# stand.net
KiCad netlist of a schematic drawn in Altium Designer
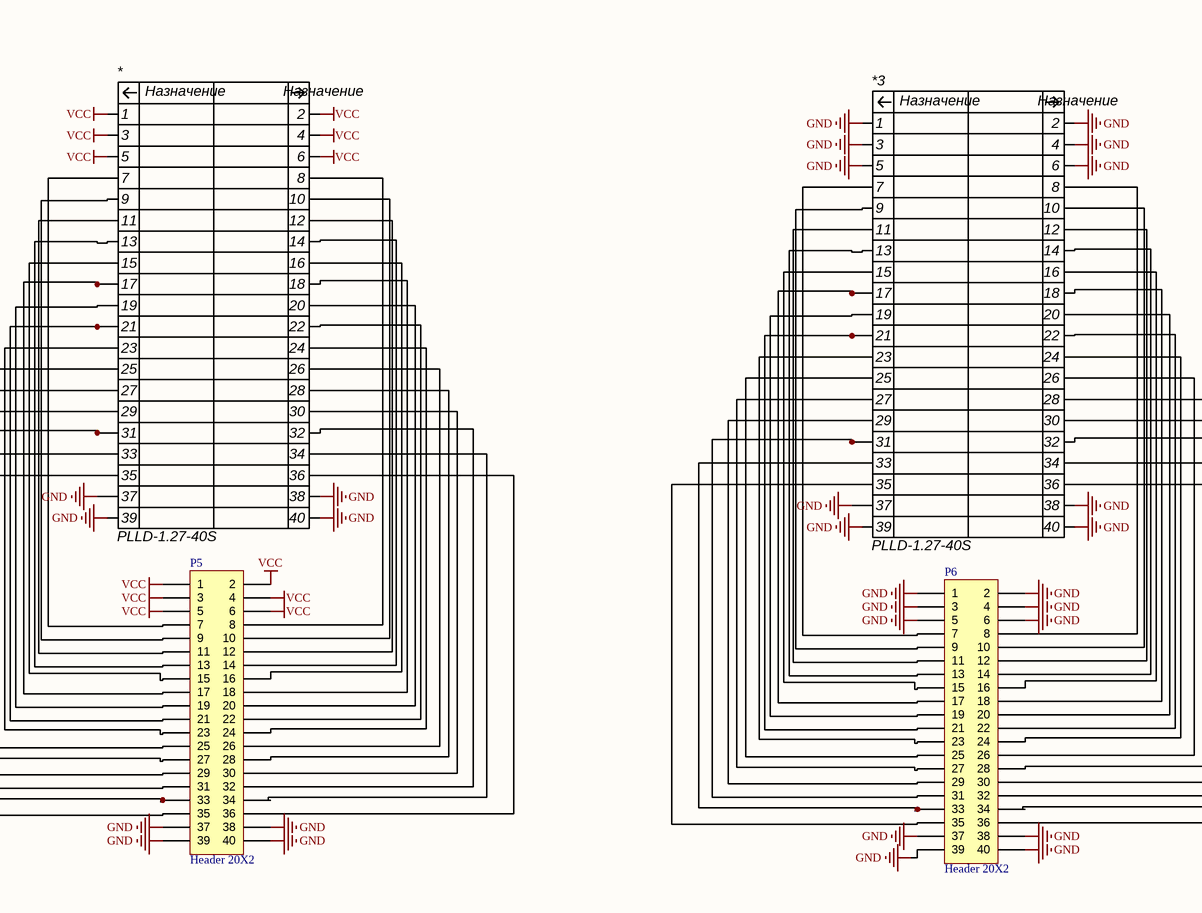
[diagram p0: stand.SchDoc, left]
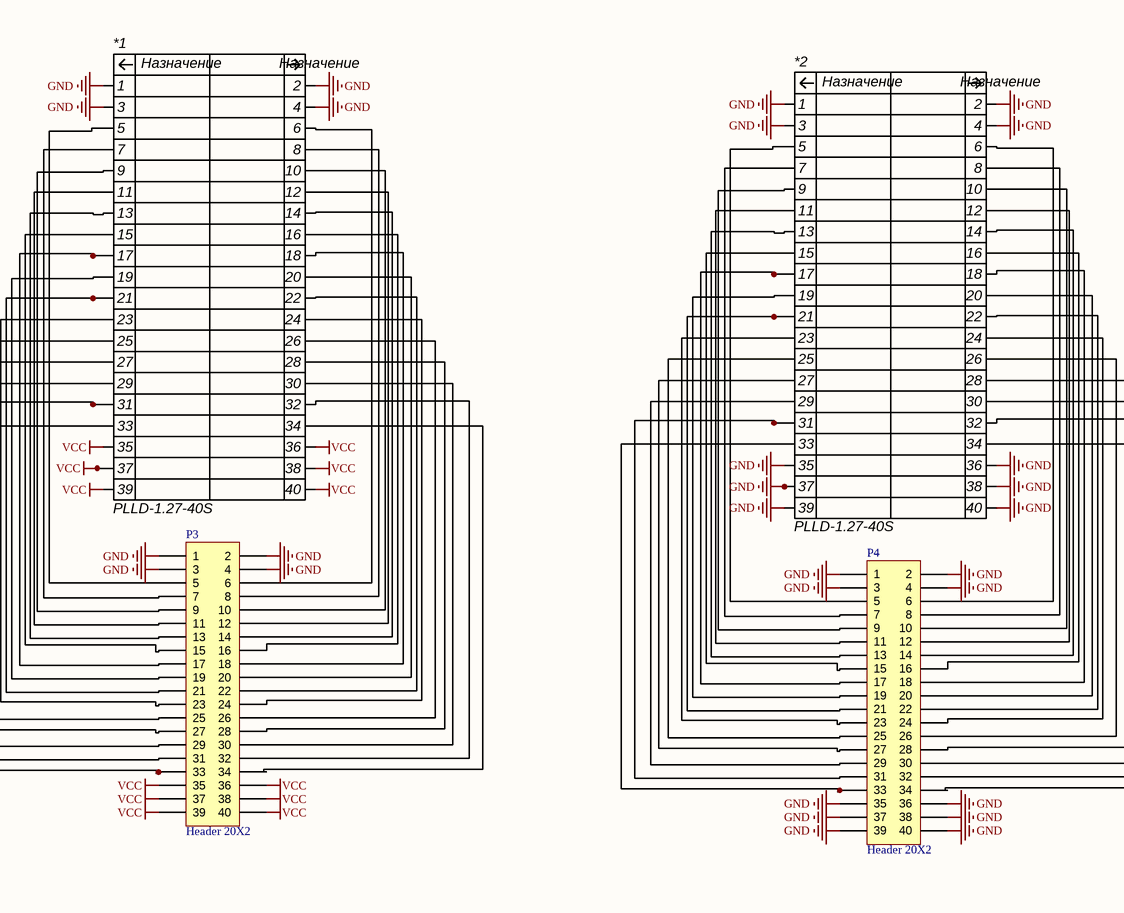
[diagram p1: stand.SchDoc, right]

(export (version "E")
  (design (tool "Eeschema 10.0.6"))
  (components
    (comp (ref "*")
      (value "PLLD-1.27-40S")
      (footprint "Headr 2x20 male")
      (libsource (lib "Разьемы_PLLD_PBD") (part "PLLD-1.27-40S"))
    )
    (comp (ref "*1")
      (value "PLLD-1.27-40S")
      (footprint "Headr 2x20 male")
      (libsource (lib "Разьемы_PLLD_PBD") (part "PLLD-1.27-40S"))
    )
    (comp (ref "*2")
      (value "PLLD-1.27-40S")
      (footprint "Headr 2x20 male")
      (libsource (lib "Разьемы_PLLD_PBD") (part "PLLD-1.27-40S"))
    )
    (comp (ref "*3")
      (value "PLLD-1.27-40S")
      (footprint "Headr 2x20 male")
      (libsource (lib "Разьемы_PLLD_PBD") (part "PLLD-1.27-40S"))
    )
    (comp (ref "P3")
      (value "Header 20X2")
      (footprint "HDR2X20")
      (description "Header, 20-Pin, Dual row")
      (fields (field (name "PUBLISHER") "Altium Limited"))
      (libsource (lib "Miscellaneous Connectors") (part "Header 20X2"))
    )
    (comp (ref "P4")
      (value "Header 20X2")
      (footprint "HDR2X20")
      (description "Header, 20-Pin, Dual row")
      (fields (field (name "PUBLISHER") "Altium Limited"))
      (libsource (lib "Miscellaneous Connectors") (part "Header 20X2"))
    )
    (comp (ref "P5")
      (value "Header 20X2")
      (footprint "HDR2X20")
      (description "Header, 20-Pin, Dual row")
      (fields (field (name "PUBLISHER") "Altium Limited"))
      (libsource (lib "Miscellaneous Connectors") (part "Header 20X2"))
    )
    (comp (ref "P6")
      (value "Header 20X2")
      (footprint "HDR2X20")
      (description "Header, 20-Pin, Dual row")
      (fields (field (name "PUBLISHER") "Altium Limited"))
      (libsource (lib "Miscellaneous Connectors") (part "Header 20X2"))
    )
  )
  (nets
    (net (code "1") (name "GND") (class "Default")
      (node (ref "*") (pin "37") (pinfunction "37_37") (pintype "passive"))
      (node (ref "*") (pin "38") (pinfunction "38_38") (pintype "passive"))
      (node (ref "*") (pin "39") (pinfunction "39_39") (pintype "passive"))
      (node (ref "*") (pin "40") (pinfunction "40_40") (pintype "passive"))
      (node (ref "*1") (pin "1") (pinfunction "1_1") (pintype "passive"))
      (node (ref "*1") (pin "2") (pinfunction "2_2") (pintype "passive"))
      (node (ref "*1") (pin "3") (pinfunction "3_3") (pintype "passive"))
      (node (ref "*1") (pin "4") (pinfunction "4_4") (pintype "passive"))
      (node (ref "*2") (pin "1") (pinfunction "1_1") (pintype "passive"))
      (node (ref "*2") (pin "2") (pinfunction "2_2") (pintype "passive"))
      (node (ref "*2") (pin "3") (pinfunction "3_3") (pintype "passive"))
      (node (ref "*2") (pin "35") (pinfunction "35_35") (pintype "passive"))
      (node (ref "*2") (pin "36") (pinfunction "36_36") (pintype "passive"))
      (node (ref "*2") (pin "37") (pinfunction "37_37") (pintype "passive"))
      (node (ref "*2") (pin "38") (pinfunction "38_38") (pintype "passive"))
      (node (ref "*2") (pin "39") (pinfunction "39_39") (pintype "passive"))
      (node (ref "*2") (pin "4") (pinfunction "4_4") (pintype "passive"))
      (node (ref "*2") (pin "40") (pinfunction "40_40") (pintype "passive"))
      (node (ref "*3") (pin "1") (pinfunction "1_1") (pintype "passive"))
      (node (ref "*3") (pin "2") (pinfunction "2_2") (pintype "passive"))
      (node (ref "*3") (pin "3") (pinfunction "3_3") (pintype "passive"))
      (node (ref "*3") (pin "37") (pinfunction "37_37") (pintype "passive"))
      (node (ref "*3") (pin "38") (pinfunction "38_38") (pintype "passive"))
      (node (ref "*3") (pin "39") (pinfunction "39_39") (pintype "passive"))
      (node (ref "*3") (pin "4") (pinfunction "4_4") (pintype "passive"))
      (node (ref "*3") (pin "40") (pinfunction "40_40") (pintype "passive"))
      (node (ref "*3") (pin "5") (pinfunction "5_5") (pintype "passive"))
      (node (ref "*3") (pin "6") (pinfunction "6_6") (pintype "passive"))
      (node (ref "P3") (pin "1") (pinfunction "1_1") (pintype "passive"))
      (node (ref "P3") (pin "2") (pinfunction "2_2") (pintype "passive"))
      (node (ref "P3") (pin "3") (pinfunction "3_3") (pintype "passive"))
      (node (ref "P3") (pin "4") (pinfunction "4_4") (pintype "passive"))
      (node (ref "P4") (pin "1") (pinfunction "1_1") (pintype "passive"))
      (node (ref "P4") (pin "2") (pinfunction "2_2") (pintype "passive"))
      (node (ref "P4") (pin "3") (pinfunction "3_3") (pintype "passive"))
      (node (ref "P4") (pin "35") (pinfunction "35_35") (pintype "passive"))
      (node (ref "P4") (pin "36") (pinfunction "36_36") (pintype "passive"))
      (node (ref "P4") (pin "37") (pinfunction "37_37") (pintype "passive"))
      (node (ref "P4") (pin "38") (pinfunction "38_38") (pintype "passive"))
      (node (ref "P4") (pin "39") (pinfunction "39_39") (pintype "passive"))
      (node (ref "P4") (pin "4") (pinfunction "4_4") (pintype "passive"))
      (node (ref "P4") (pin "40") (pinfunction "40_40") (pintype "passive"))
      (node (ref "P5") (pin "37") (pinfunction "37_37") (pintype "passive"))
      (node (ref "P5") (pin "38") (pinfunction "38_38") (pintype "passive"))
      (node (ref "P5") (pin "39") (pinfunction "39_39") (pintype "passive"))
      (node (ref "P5") (pin "40") (pinfunction "40_40") (pintype "passive"))
      (node (ref "P6") (pin "1") (pinfunction "1_1") (pintype "passive"))
      (node (ref "P6") (pin "2") (pinfunction "2_2") (pintype "passive"))
      (node (ref "P6") (pin "3") (pinfunction "3_3") (pintype "passive"))
      (node (ref "P6") (pin "37") (pinfunction "37_37") (pintype "passive"))
      (node (ref "P6") (pin "38") (pinfunction "38_38") (pintype "passive"))
      (node (ref "P6") (pin "39") (pinfunction "39_39") (pintype "passive"))
      (node (ref "P6") (pin "4") (pinfunction "4_4") (pintype "passive"))
      (node (ref "P6") (pin "40") (pinfunction "40_40") (pintype "passive"))
      (node (ref "P6") (pin "5") (pinfunction "5_5") (pintype "passive"))
      (node (ref "P6") (pin "6") (pinfunction "6_6") (pintype "passive"))
    )
    (net (code "2") (name "Net-(*-Pad7)") (class "Default")
      (node (ref "*") (pin "7") (pinfunction "7_7") (pintype "passive"))
      (node (ref "P5") (pin "7") (pinfunction "7_7") (pintype "passive"))
    )
    (net (code "3") (name "Net-(*-Pad8)") (class "Default")
      (node (ref "*") (pin "8") (pinfunction "8_8") (pintype "passive"))
      (node (ref "P5") (pin "8") (pinfunction "8_8") (pintype "passive"))
    )
    (net (code "4") (name "Net-(*-Pad9)") (class "Default")
      (node (ref "*") (pin "9") (pinfunction "9_9") (pintype "passive"))
      (node (ref "P5") (pin "9") (pinfunction "9_9") (pintype "passive"))
    )
    (net (code "5") (name "Net-(*-Pad10)") (class "Default")
      (node (ref "*") (pin "10") (pinfunction "10_10") (pintype "passive"))
      (node (ref "P5") (pin "10") (pinfunction "10_10") (pintype "passive"))
    )
    (net (code "6") (name "Net-(*-Pad11)") (class "Default")
      (node (ref "*") (pin "11") (pinfunction "11_11") (pintype "passive"))
      (node (ref "P5") (pin "11") (pinfunction "11_11") (pintype "passive"))
    )
    (net (code "7") (name "Net-(*-Pad12)") (class "Default")
      (node (ref "*") (pin "12") (pinfunction "12_12") (pintype "passive"))
      (node (ref "P5") (pin "12") (pinfunction "12_12") (pintype "passive"))
    )
    (net (code "8") (name "Net-(*-Pad13)") (class "Default")
      (node (ref "*") (pin "13") (pinfunction "13_13") (pintype "passive"))
      (node (ref "P5") (pin "13") (pinfunction "13_13") (pintype "passive"))
    )
    (net (code "9") (name "Net-(*-Pad14)") (class "Default")
      (node (ref "*") (pin "14") (pinfunction "14_14") (pintype "passive"))
      (node (ref "P5") (pin "14") (pinfunction "14_14") (pintype "passive"))
    )
    (net (code "10") (name "Net-(*-Pad15)") (class "Default")
      (node (ref "*") (pin "15") (pinfunction "15_15") (pintype "passive"))
      (node (ref "P5") (pin "15") (pinfunction "15_15") (pintype "passive"))
    )
    (net (code "11") (name "Net-(*-Pad16)") (class "Default")
      (node (ref "*") (pin "16") (pinfunction "16_16") (pintype "passive"))
      (node (ref "P5") (pin "16") (pinfunction "16_16") (pintype "passive"))
    )
    (net (code "12") (name "Net-(*-Pad17)") (class "Default")
      (node (ref "*") (pin "17") (pinfunction "17_17") (pintype "passive"))
      (node (ref "P5") (pin "17") (pinfunction "17_17") (pintype "passive"))
    )
    (net (code "13") (name "Net-(*-Pad18)") (class "Default")
      (node (ref "*") (pin "18") (pinfunction "18_18") (pintype "passive"))
      (node (ref "P5") (pin "18") (pinfunction "18_18") (pintype "passive"))
    )
    (net (code "14") (name "Net-(*-Pad19)") (class "Default")
      (node (ref "*") (pin "19") (pinfunction "19_19") (pintype "passive"))
      (node (ref "P5") (pin "19") (pinfunction "19_19") (pintype "passive"))
    )
    (net (code "15") (name "Net-(*-Pad20)") (class "Default")
      (node (ref "*") (pin "20") (pinfunction "20_20") (pintype "passive"))
      (node (ref "P5") (pin "20") (pinfunction "20_20") (pintype "passive"))
    )
    (net (code "16") (name "Net-(*-Pad21)") (class "Default")
      (node (ref "*") (pin "21") (pinfunction "21_21") (pintype "passive"))
      (node (ref "P5") (pin "21") (pinfunction "21_21") (pintype "passive"))
    )
    (net (code "17") (name "Net-(*-Pad22)") (class "Default")
      (node (ref "*") (pin "22") (pinfunction "22_22") (pintype "passive"))
      (node (ref "P5") (pin "22") (pinfunction "22_22") (pintype "passive"))
    )
    (net (code "18") (name "Net-(*-Pad23)") (class "Default")
      (node (ref "*") (pin "23") (pinfunction "23_23") (pintype "passive"))
      (node (ref "P5") (pin "23") (pinfunction "23_23") (pintype "passive"))
    )
    (net (code "19") (name "Net-(*-Pad24)") (class "Default")
      (node (ref "*") (pin "24") (pinfunction "24_24") (pintype "passive"))
      (node (ref "P5") (pin "24") (pinfunction "24_24") (pintype "passive"))
    )
    (net (code "20") (name "Net-(*-Pad25)") (class "Default")
      (node (ref "*") (pin "25") (pinfunction "25_25") (pintype "passive"))
      (node (ref "P5") (pin "25") (pinfunction "25_25") (pintype "passive"))
    )
    (net (code "21") (name "Net-(*-Pad26)") (class "Default")
      (node (ref "*") (pin "26") (pinfunction "26_26") (pintype "passive"))
      (node (ref "P5") (pin "26") (pinfunction "26_26") (pintype "passive"))
    )
    (net (code "22") (name "Net-(*-Pad27)") (class "Default")
      (node (ref "*") (pin "27") (pinfunction "27_27") (pintype "passive"))
      (node (ref "P5") (pin "27") (pinfunction "27_27") (pintype "passive"))
    )
    (net (code "23") (name "Net-(*-Pad28)") (class "Default")
      (node (ref "*") (pin "28") (pinfunction "28_28") (pintype "passive"))
      (node (ref "P5") (pin "28") (pinfunction "28_28") (pintype "passive"))
    )
    (net (code "24") (name "Net-(*-Pad29)") (class "Default")
      (node (ref "*") (pin "29") (pinfunction "29_29") (pintype "passive"))
      (node (ref "P5") (pin "29") (pinfunction "29_29") (pintype "passive"))
    )
    (net (code "25") (name "Net-(*-Pad30)") (class "Default")
      (node (ref "*") (pin "30") (pinfunction "30_30") (pintype "passive"))
      (node (ref "P5") (pin "30") (pinfunction "30_30") (pintype "passive"))
    )
    (net (code "26") (name "Net-(*-Pad31)") (class "Default")
      (node (ref "*") (pin "31") (pinfunction "31_31") (pintype "passive"))
      (node (ref "P5") (pin "31") (pinfunction "31_31") (pintype "passive"))
    )
    (net (code "27") (name "Net-(*-Pad32)") (class "Default")
      (node (ref "*") (pin "32") (pinfunction "32_32") (pintype "passive"))
      (node (ref "P5") (pin "32") (pinfunction "32_32") (pintype "passive"))
    )
    (net (code "28") (name "Net-(*-Pad33)") (class "Default")
      (node (ref "*") (pin "33") (pinfunction "33_33") (pintype "passive"))
      (node (ref "P5") (pin "33") (pinfunction "33_33") (pintype "passive"))
    )
    (net (code "29") (name "Net-(*-Pad34)") (class "Default")
      (node (ref "*") (pin "34") (pinfunction "34_34") (pintype "passive"))
      (node (ref "P5") (pin "34") (pinfunction "34_34") (pintype "passive"))
    )
    (net (code "30") (name "Net-(*-Pad35)") (class "Default")
      (node (ref "*") (pin "35") (pinfunction "35_35") (pintype "passive"))
      (node (ref "P5") (pin "35") (pinfunction "35_35") (pintype "passive"))
    )
    (net (code "31") (name "Net-(*-Pad36)") (class "Default")
      (node (ref "*") (pin "36") (pinfunction "36_36") (pintype "passive"))
      (node (ref "P5") (pin "36") (pinfunction "36_36") (pintype "passive"))
    )
    (net (code "32") (name "Net-(*1-Pad5)") (class "Default")
      (node (ref "*1") (pin "5") (pinfunction "5_5") (pintype "passive"))
      (node (ref "P3") (pin "5") (pinfunction "5_5") (pintype "passive"))
    )
    (net (code "33") (name "Net-(*1-Pad6)") (class "Default")
      (node (ref "*1") (pin "6") (pinfunction "6_6") (pintype "passive"))
      (node (ref "P3") (pin "6") (pinfunction "6_6") (pintype "passive"))
    )
    (net (code "34") (name "Net-(*1-Pad7)") (class "Default")
      (node (ref "*1") (pin "7") (pinfunction "7_7") (pintype "passive"))
      (node (ref "P3") (pin "7") (pinfunction "7_7") (pintype "passive"))
    )
    (net (code "35") (name "Net-(*1-Pad8)") (class "Default")
      (node (ref "*1") (pin "8") (pinfunction "8_8") (pintype "passive"))
      (node (ref "P3") (pin "8") (pinfunction "8_8") (pintype "passive"))
    )
    (net (code "36") (name "Net-(*1-Pad9)") (class "Default")
      (node (ref "*1") (pin "9") (pinfunction "9_9") (pintype "passive"))
      (node (ref "P3") (pin "9") (pinfunction "9_9") (pintype "passive"))
    )
    (net (code "37") (name "Net-(*1-Pad10)") (class "Default")
      (node (ref "*1") (pin "10") (pinfunction "10_10") (pintype "passive"))
      (node (ref "P3") (pin "10") (pinfunction "10_10") (pintype "passive"))
    )
    (net (code "38") (name "Net-(*1-Pad11)") (class "Default")
      (node (ref "*1") (pin "11") (pinfunction "11_11") (pintype "passive"))
      (node (ref "P3") (pin "11") (pinfunction "11_11") (pintype "passive"))
    )
    (net (code "39") (name "Net-(*1-Pad12)") (class "Default")
      (node (ref "*1") (pin "12") (pinfunction "12_12") (pintype "passive"))
      (node (ref "P3") (pin "12") (pinfunction "12_12") (pintype "passive"))
    )
    (net (code "40") (name "Net-(*1-Pad13)") (class "Default")
      (node (ref "*1") (pin "13") (pinfunction "13_13") (pintype "passive"))
      (node (ref "P3") (pin "13") (pinfunction "13_13") (pintype "passive"))
    )
    (net (code "41") (name "Net-(*1-Pad14)") (class "Default")
      (node (ref "*1") (pin "14") (pinfunction "14_14") (pintype "passive"))
      (node (ref "P3") (pin "14") (pinfunction "14_14") (pintype "passive"))
    )
    (net (code "42") (name "Net-(*1-Pad15)") (class "Default")
      (node (ref "*1") (pin "15") (pinfunction "15_15") (pintype "passive"))
      (node (ref "P3") (pin "15") (pinfunction "15_15") (pintype "passive"))
    )
    (net (code "43") (name "Net-(*1-Pad16)") (class "Default")
      (node (ref "*1") (pin "16") (pinfunction "16_16") (pintype "passive"))
      (node (ref "P3") (pin "16") (pinfunction "16_16") (pintype "passive"))
    )
    (net (code "44") (name "Net-(*1-Pad17)") (class "Default")
      (node (ref "*1") (pin "17") (pinfunction "17_17") (pintype "passive"))
      (node (ref "P3") (pin "17") (pinfunction "17_17") (pintype "passive"))
    )
    (net (code "45") (name "Net-(*1-Pad18)") (class "Default")
      (node (ref "*1") (pin "18") (pinfunction "18_18") (pintype "passive"))
      (node (ref "P3") (pin "18") (pinfunction "18_18") (pintype "passive"))
    )
    (net (code "46") (name "Net-(*1-Pad19)") (class "Default")
      (node (ref "*1") (pin "19") (pinfunction "19_19") (pintype "passive"))
      (node (ref "P3") (pin "19") (pinfunction "19_19") (pintype "passive"))
    )
    (net (code "47") (name "Net-(*1-Pad20)") (class "Default")
      (node (ref "*1") (pin "20") (pinfunction "20_20") (pintype "passive"))
      (node (ref "P3") (pin "20") (pinfunction "20_20") (pintype "passive"))
    )
    (net (code "48") (name "Net-(*1-Pad21)") (class "Default")
      (node (ref "*1") (pin "21") (pinfunction "21_21") (pintype "passive"))
      (node (ref "P3") (pin "21") (pinfunction "21_21") (pintype "passive"))
    )
    (net (code "49") (name "Net-(*1-Pad22)") (class "Default")
      (node (ref "*1") (pin "22") (pinfunction "22_22") (pintype "passive"))
      (node (ref "P3") (pin "22") (pinfunction "22_22") (pintype "passive"))
    )
    (net (code "50") (name "Net-(*1-Pad23)") (class "Default")
      (node (ref "*1") (pin "23") (pinfunction "23_23") (pintype "passive"))
      (node (ref "P3") (pin "23") (pinfunction "23_23") (pintype "passive"))
    )
    (net (code "51") (name "Net-(*1-Pad24)") (class "Default")
      (node (ref "*1") (pin "24") (pinfunction "24_24") (pintype "passive"))
      (node (ref "P3") (pin "24") (pinfunction "24_24") (pintype "passive"))
    )
    (net (code "52") (name "Net-(*1-Pad25)") (class "Default")
      (node (ref "*1") (pin "25") (pinfunction "25_25") (pintype "passive"))
      (node (ref "P3") (pin "25") (pinfunction "25_25") (pintype "passive"))
    )
    (net (code "53") (name "Net-(*1-Pad26)") (class "Default")
      (node (ref "*1") (pin "26") (pinfunction "26_26") (pintype "passive"))
      (node (ref "P3") (pin "26") (pinfunction "26_26") (pintype "passive"))
    )
    (net (code "54") (name "Net-(*1-Pad27)") (class "Default")
      (node (ref "*1") (pin "27") (pinfunction "27_27") (pintype "passive"))
      (node (ref "P3") (pin "27") (pinfunction "27_27") (pintype "passive"))
    )
    (net (code "55") (name "Net-(*1-Pad28)") (class "Default")
      (node (ref "*1") (pin "28") (pinfunction "28_28") (pintype "passive"))
      (node (ref "P3") (pin "28") (pinfunction "28_28") (pintype "passive"))
    )
    (net (code "56") (name "Net-(*1-Pad29)") (class "Default")
      (node (ref "*1") (pin "29") (pinfunction "29_29") (pintype "passive"))
      (node (ref "P3") (pin "29") (pinfunction "29_29") (pintype "passive"))
    )
    (net (code "57") (name "Net-(*1-Pad30)") (class "Default")
      (node (ref "*1") (pin "30") (pinfunction "30_30") (pintype "passive"))
      (node (ref "P3") (pin "30") (pinfunction "30_30") (pintype "passive"))
    )
    (net (code "58") (name "Net-(*1-Pad31)") (class "Default")
      (node (ref "*1") (pin "31") (pinfunction "31_31") (pintype "passive"))
      (node (ref "P3") (pin "31") (pinfunction "31_31") (pintype "passive"))
    )
    (net (code "59") (name "Net-(*1-Pad32)") (class "Default")
      (node (ref "*1") (pin "32") (pinfunction "32_32") (pintype "passive"))
      (node (ref "P3") (pin "32") (pinfunction "32_32") (pintype "passive"))
    )
    (net (code "60") (name "Net-(*1-Pad33)") (class "Default")
      (node (ref "*1") (pin "33") (pinfunction "33_33") (pintype "passive"))
      (node (ref "P3") (pin "33") (pinfunction "33_33") (pintype "passive"))
    )
    (net (code "61") (name "Net-(*1-Pad34)") (class "Default")
      (node (ref "*1") (pin "34") (pinfunction "34_34") (pintype "passive"))
      (node (ref "P3") (pin "34") (pinfunction "34_34") (pintype "passive"))
    )
    (net (code "62") (name "Net-(*2-Pad5)") (class "Default")
      (node (ref "*2") (pin "5") (pinfunction "5_5") (pintype "passive"))
      (node (ref "P4") (pin "5") (pinfunction "5_5") (pintype "passive"))
    )
    (net (code "63") (name "Net-(*2-Pad6)") (class "Default")
      (node (ref "*2") (pin "6") (pinfunction "6_6") (pintype "passive"))
      (node (ref "P4") (pin "6") (pinfunction "6_6") (pintype "passive"))
    )
    (net (code "64") (name "Net-(*2-Pad7)") (class "Default")
      (node (ref "*2") (pin "7") (pinfunction "7_7") (pintype "passive"))
      (node (ref "P4") (pin "7") (pinfunction "7_7") (pintype "passive"))
    )
    (net (code "65") (name "Net-(*2-Pad8)") (class "Default")
      (node (ref "*2") (pin "8") (pinfunction "8_8") (pintype "passive"))
      (node (ref "P4") (pin "8") (pinfunction "8_8") (pintype "passive"))
    )
    (net (code "66") (name "Net-(*2-Pad9)") (class "Default")
      (node (ref "*2") (pin "9") (pinfunction "9_9") (pintype "passive"))
      (node (ref "P4") (pin "9") (pinfunction "9_9") (pintype "passive"))
    )
    (net (code "67") (name "Net-(*2-Pad10)") (class "Default")
      (node (ref "*2") (pin "10") (pinfunction "10_10") (pintype "passive"))
      (node (ref "P4") (pin "10") (pinfunction "10_10") (pintype "passive"))
    )
    (net (code "68") (name "Net-(*2-Pad11)") (class "Default")
      (node (ref "*2") (pin "11") (pinfunction "11_11") (pintype "passive"))
      (node (ref "P4") (pin "11") (pinfunction "11_11") (pintype "passive"))
    )
    (net (code "69") (name "Net-(*2-Pad12)") (class "Default")
      (node (ref "*2") (pin "12") (pinfunction "12_12") (pintype "passive"))
      (node (ref "P4") (pin "12") (pinfunction "12_12") (pintype "passive"))
    )
    (net (code "70") (name "Net-(*2-Pad13)") (class "Default")
      (node (ref "*2") (pin "13") (pinfunction "13_13") (pintype "passive"))
      (node (ref "P4") (pin "13") (pinfunction "13_13") (pintype "passive"))
    )
    (net (code "71") (name "Net-(*2-Pad14)") (class "Default")
      (node (ref "*2") (pin "14") (pinfunction "14_14") (pintype "passive"))
      (node (ref "P4") (pin "14") (pinfunction "14_14") (pintype "passive"))
    )
    (net (code "72") (name "Net-(*2-Pad15)") (class "Default")
      (node (ref "*2") (pin "15") (pinfunction "15_15") (pintype "passive"))
      (node (ref "P4") (pin "15") (pinfunction "15_15") (pintype "passive"))
    )
    (net (code "73") (name "Net-(*2-Pad16)") (class "Default")
      (node (ref "*2") (pin "16") (pinfunction "16_16") (pintype "passive"))
      (node (ref "P4") (pin "16") (pinfunction "16_16") (pintype "passive"))
    )
    (net (code "74") (name "Net-(*2-Pad17)") (class "Default")
      (node (ref "*2") (pin "17") (pinfunction "17_17") (pintype "passive"))
      (node (ref "P4") (pin "17") (pinfunction "17_17") (pintype "passive"))
    )
    (net (code "75") (name "Net-(*2-Pad18)") (class "Default")
      (node (ref "*2") (pin "18") (pinfunction "18_18") (pintype "passive"))
      (node (ref "P4") (pin "18") (pinfunction "18_18") (pintype "passive"))
    )
    (net (code "76") (name "Net-(*2-Pad19)") (class "Default")
      (node (ref "*2") (pin "19") (pinfunction "19_19") (pintype "passive"))
      (node (ref "P4") (pin "19") (pinfunction "19_19") (pintype "passive"))
    )
    (net (code "77") (name "Net-(*2-Pad20)") (class "Default")
      (node (ref "*2") (pin "20") (pinfunction "20_20") (pintype "passive"))
      (node (ref "P4") (pin "20") (pinfunction "20_20") (pintype "passive"))
    )
    (net (code "78") (name "Net-(*2-Pad21)") (class "Default")
      (node (ref "*2") (pin "21") (pinfunction "21_21") (pintype "passive"))
      (node (ref "P4") (pin "21") (pinfunction "21_21") (pintype "passive"))
    )
    (net (code "79") (name "Net-(*2-Pad22)") (class "Default")
      (node (ref "*2") (pin "22") (pinfunction "22_22") (pintype "passive"))
      (node (ref "P4") (pin "22") (pinfunction "22_22") (pintype "passive"))
    )
    (net (code "80") (name "Net-(*2-Pad23)") (class "Default")
      (node (ref "*2") (pin "23") (pinfunction "23_23") (pintype "passive"))
      (node (ref "P4") (pin "23") (pinfunction "23_23") (pintype "passive"))
    )
    (net (code "81") (name "Net-(*2-Pad24)") (class "Default")
      (node (ref "*2") (pin "24") (pinfunction "24_24") (pintype "passive"))
      (node (ref "P4") (pin "24") (pinfunction "24_24") (pintype "passive"))
    )
    (net (code "82") (name "Net-(*2-Pad25)") (class "Default")
      (node (ref "*2") (pin "25") (pinfunction "25_25") (pintype "passive"))
      (node (ref "P4") (pin "25") (pinfunction "25_25") (pintype "passive"))
    )
    (net (code "83") (name "Net-(*2-Pad26)") (class "Default")
      (node (ref "*2") (pin "26") (pinfunction "26_26") (pintype "passive"))
      (node (ref "P4") (pin "26") (pinfunction "26_26") (pintype "passive"))
    )
    (net (code "84") (name "Net-(*2-Pad27)") (class "Default")
      (node (ref "*2") (pin "27") (pinfunction "27_27") (pintype "passive"))
      (node (ref "P4") (pin "27") (pinfunction "27_27") (pintype "passive"))
    )
    (net (code "85") (name "Net-(*2-Pad28)") (class "Default")
      (node (ref "*2") (pin "28") (pinfunction "28_28") (pintype "passive"))
      (node (ref "P4") (pin "28") (pinfunction "28_28") (pintype "passive"))
    )
    (net (code "86") (name "Net-(*2-Pad29)") (class "Default")
      (node (ref "*2") (pin "29") (pinfunction "29_29") (pintype "passive"))
      (node (ref "P4") (pin "29") (pinfunction "29_29") (pintype "passive"))
    )
    (net (code "87") (name "Net-(*2-Pad30)") (class "Default")
      (node (ref "*2") (pin "30") (pinfunction "30_30") (pintype "passive"))
      (node (ref "P4") (pin "30") (pinfunction "30_30") (pintype "passive"))
    )
    (net (code "88") (name "Net-(*2-Pad31)") (class "Default")
      (node (ref "*2") (pin "31") (pinfunction "31_31") (pintype "passive"))
      (node (ref "P4") (pin "31") (pinfunction "31_31") (pintype "passive"))
    )
    (net (code "89") (name "Net-(*2-Pad32)") (class "Default")
      (node (ref "*2") (pin "32") (pinfunction "32_32") (pintype "passive"))
      (node (ref "P4") (pin "32") (pinfunction "32_32") (pintype "passive"))
    )
    (net (code "90") (name "Net-(*2-Pad33)") (class "Default")
      (node (ref "*2") (pin "33") (pinfunction "33_33") (pintype "passive"))
      (node (ref "P4") (pin "33") (pinfunction "33_33") (pintype "passive"))
    )
    (net (code "91") (name "Net-(*2-Pad34)") (class "Default")
      (node (ref "*2") (pin "34") (pinfunction "34_34") (pintype "passive"))
      (node (ref "P4") (pin "34") (pinfunction "34_34") (pintype "passive"))
    )
    (net (code "92") (name "Net-(*3-Pad7)") (class "Default")
      (node (ref "*3") (pin "7") (pinfunction "7_7") (pintype "passive"))
      (node (ref "P6") (pin "7") (pinfunction "7_7") (pintype "passive"))
    )
    (net (code "93") (name "Net-(*3-Pad8)") (class "Default")
      (node (ref "*3") (pin "8") (pinfunction "8_8") (pintype "passive"))
      (node (ref "P6") (pin "8") (pinfunction "8_8") (pintype "passive"))
    )
    (net (code "94") (name "Net-(*3-Pad9)") (class "Default")
      (node (ref "*3") (pin "9") (pinfunction "9_9") (pintype "passive"))
      (node (ref "P6") (pin "9") (pinfunction "9_9") (pintype "passive"))
    )
    (net (code "95") (name "Net-(*3-Pad10)") (class "Default")
      (node (ref "*3") (pin "10") (pinfunction "10_10") (pintype "passive"))
      (node (ref "P6") (pin "10") (pinfunction "10_10") (pintype "passive"))
    )
    (net (code "96") (name "Net-(*3-Pad11)") (class "Default")
      (node (ref "*3") (pin "11") (pinfunction "11_11") (pintype "passive"))
      (node (ref "P6") (pin "11") (pinfunction "11_11") (pintype "passive"))
    )
    (net (code "97") (name "Net-(*3-Pad12)") (class "Default")
      (node (ref "*3") (pin "12") (pinfunction "12_12") (pintype "passive"))
      (node (ref "P6") (pin "12") (pinfunction "12_12") (pintype "passive"))
    )
    (net (code "98") (name "Net-(*3-Pad13)") (class "Default")
      (node (ref "*3") (pin "13") (pinfunction "13_13") (pintype "passive"))
      (node (ref "P6") (pin "13") (pinfunction "13_13") (pintype "passive"))
    )
    (net (code "99") (name "Net-(*3-Pad14)") (class "Default")
      (node (ref "*3") (pin "14") (pinfunction "14_14") (pintype "passive"))
      (node (ref "P6") (pin "14") (pinfunction "14_14") (pintype "passive"))
    )
    (net (code "100") (name "Net-(*3-Pad15)") (class "Default")
      (node (ref "*3") (pin "15") (pinfunction "15_15") (pintype "passive"))
      (node (ref "P6") (pin "15") (pinfunction "15_15") (pintype "passive"))
    )
    (net (code "101") (name "Net-(*3-Pad16)") (class "Default")
      (node (ref "*3") (pin "16") (pinfunction "16_16") (pintype "passive"))
      (node (ref "P6") (pin "16") (pinfunction "16_16") (pintype "passive"))
    )
    (net (code "102") (name "Net-(*3-Pad17)") (class "Default")
      (node (ref "*3") (pin "17") (pinfunction "17_17") (pintype "passive"))
      (node (ref "P6") (pin "17") (pinfunction "17_17") (pintype "passive"))
    )
    (net (code "103") (name "Net-(*3-Pad18)") (class "Default")
      (node (ref "*3") (pin "18") (pinfunction "18_18") (pintype "passive"))
      (node (ref "P6") (pin "18") (pinfunction "18_18") (pintype "passive"))
    )
    (net (code "104") (name "Net-(*3-Pad19)") (class "Default")
      (node (ref "*3") (pin "19") (pinfunction "19_19") (pintype "passive"))
      (node (ref "P6") (pin "19") (pinfunction "19_19") (pintype "passive"))
    )
    (net (code "105") (name "Net-(*3-Pad20)") (class "Default")
      (node (ref "*3") (pin "20") (pinfunction "20_20") (pintype "passive"))
      (node (ref "P6") (pin "20") (pinfunction "20_20") (pintype "passive"))
    )
    (net (code "106") (name "Net-(*3-Pad21)") (class "Default")
      (node (ref "*3") (pin "21") (pinfunction "21_21") (pintype "passive"))
      (node (ref "P6") (pin "21") (pinfunction "21_21") (pintype "passive"))
    )
    (net (code "107") (name "Net-(*3-Pad22)") (class "Default")
      (node (ref "*3") (pin "22") (pinfunction "22_22") (pintype "passive"))
      (node (ref "P6") (pin "22") (pinfunction "22_22") (pintype "passive"))
    )
    (net (code "108") (name "Net-(*3-Pad23)") (class "Default")
      (node (ref "*3") (pin "23") (pinfunction "23_23") (pintype "passive"))
      (node (ref "P6") (pin "23") (pinfunction "23_23") (pintype "passive"))
    )
    (net (code "109") (name "Net-(*3-Pad24)") (class "Default")
      (node (ref "*3") (pin "24") (pinfunction "24_24") (pintype "passive"))
      (node (ref "P6") (pin "24") (pinfunction "24_24") (pintype "passive"))
    )
    (net (code "110") (name "Net-(*3-Pad25)") (class "Default")
      (node (ref "*3") (pin "25") (pinfunction "25_25") (pintype "passive"))
      (node (ref "P6") (pin "25") (pinfunction "25_25") (pintype "passive"))
    )
    (net (code "111") (name "Net-(*3-Pad26)") (class "Default")
      (node (ref "*3") (pin "26") (pinfunction "26_26") (pintype "passive"))
      (node (ref "P6") (pin "26") (pinfunction "26_26") (pintype "passive"))
    )
    (net (code "112") (name "Net-(*3-Pad27)") (class "Default")
      (node (ref "*3") (pin "27") (pinfunction "27_27") (pintype "passive"))
      (node (ref "P6") (pin "27") (pinfunction "27_27") (pintype "passive"))
    )
    (net (code "113") (name "Net-(*3-Pad28)") (class "Default")
      (node (ref "*3") (pin "28") (pinfunction "28_28") (pintype "passive"))
      (node (ref "P6") (pin "28") (pinfunction "28_28") (pintype "passive"))
    )
    (net (code "114") (name "Net-(*3-Pad29)") (class "Default")
      (node (ref "*3") (pin "29") (pinfunction "29_29") (pintype "passive"))
      (node (ref "P6") (pin "29") (pinfunction "29_29") (pintype "passive"))
    )
    (net (code "115") (name "Net-(*3-Pad30)") (class "Default")
      (node (ref "*3") (pin "30") (pinfunction "30_30") (pintype "passive"))
      (node (ref "P6") (pin "30") (pinfunction "30_30") (pintype "passive"))
    )
    (net (code "116") (name "Net-(*3-Pad31)") (class "Default")
      (node (ref "*3") (pin "31") (pinfunction "31_31") (pintype "passive"))
      (node (ref "P6") (pin "31") (pinfunction "31_31") (pintype "passive"))
    )
    (net (code "117") (name "Net-(*3-Pad32)") (class "Default")
      (node (ref "*3") (pin "32") (pinfunction "32_32") (pintype "passive"))
      (node (ref "P6") (pin "32") (pinfunction "32_32") (pintype "passive"))
    )
    (net (code "118") (name "Net-(*3-Pad33)") (class "Default")
      (node (ref "*3") (pin "33") (pinfunction "33_33") (pintype "passive"))
      (node (ref "P6") (pin "33") (pinfunction "33_33") (pintype "passive"))
    )
    (net (code "119") (name "Net-(*3-Pad34)") (class "Default")
      (node (ref "*3") (pin "34") (pinfunction "34_34") (pintype "passive"))
      (node (ref "P6") (pin "34") (pinfunction "34_34") (pintype "passive"))
    )
    (net (code "120") (name "Net-(*3-Pad35)") (class "Default")
      (node (ref "*3") (pin "35") (pinfunction "35_35") (pintype "passive"))
      (node (ref "P6") (pin "35") (pinfunction "35_35") (pintype "passive"))
    )
    (net (code "121") (name "Net-(*3-Pad36)") (class "Default")
      (node (ref "*3") (pin "36") (pinfunction "36_36") (pintype "passive"))
      (node (ref "P6") (pin "36") (pinfunction "36_36") (pintype "passive"))
    )
    (net (code "122") (name "VCC") (class "Default")
      (node (ref "*") (pin "1") (pinfunction "1_1") (pintype "passive"))
      (node (ref "*") (pin "2") (pinfunction "2_2") (pintype "passive"))
      (node (ref "*") (pin "3") (pinfunction "3_3") (pintype "passive"))
      (node (ref "*") (pin "4") (pinfunction "4_4") (pintype "passive"))
      (node (ref "*") (pin "5") (pinfunction "5_5") (pintype "passive"))
      (node (ref "*") (pin "6") (pinfunction "6_6") (pintype "passive"))
      (node (ref "*1") (pin "35") (pinfunction "35_35") (pintype "passive"))
      (node (ref "*1") (pin "36") (pinfunction "36_36") (pintype "passive"))
      (node (ref "*1") (pin "37") (pinfunction "37_37") (pintype "passive"))
      (node (ref "*1") (pin "38") (pinfunction "38_38") (pintype "passive"))
      (node (ref "*1") (pin "39") (pinfunction "39_39") (pintype "passive"))
      (node (ref "*1") (pin "40") (pinfunction "40_40") (pintype "passive"))
      (node (ref "P3") (pin "35") (pinfunction "35_35") (pintype "passive"))
      (node (ref "P3") (pin "36") (pinfunction "36_36") (pintype "passive"))
      (node (ref "P3") (pin "37") (pinfunction "37_37") (pintype "passive"))
      (node (ref "P3") (pin "38") (pinfunction "38_38") (pintype "passive"))
      (node (ref "P3") (pin "39") (pinfunction "39_39") (pintype "passive"))
      (node (ref "P3") (pin "40") (pinfunction "40_40") (pintype "passive"))
      (node (ref "P5") (pin "1") (pinfunction "1_1") (pintype "passive"))
      (node (ref "P5") (pin "2") (pinfunction "2_2") (pintype "passive"))
      (node (ref "P5") (pin "3") (pinfunction "3_3") (pintype "passive"))
      (node (ref "P5") (pin "4") (pinfunction "4_4") (pintype "passive"))
      (node (ref "P5") (pin "5") (pinfunction "5_5") (pintype "passive"))
      (node (ref "P5") (pin "6") (pinfunction "6_6") (pintype "passive"))
    )
  )
)
